# Actuator_Base_Board.net
KiCad netlist of a schematic drawn in Altium Designer
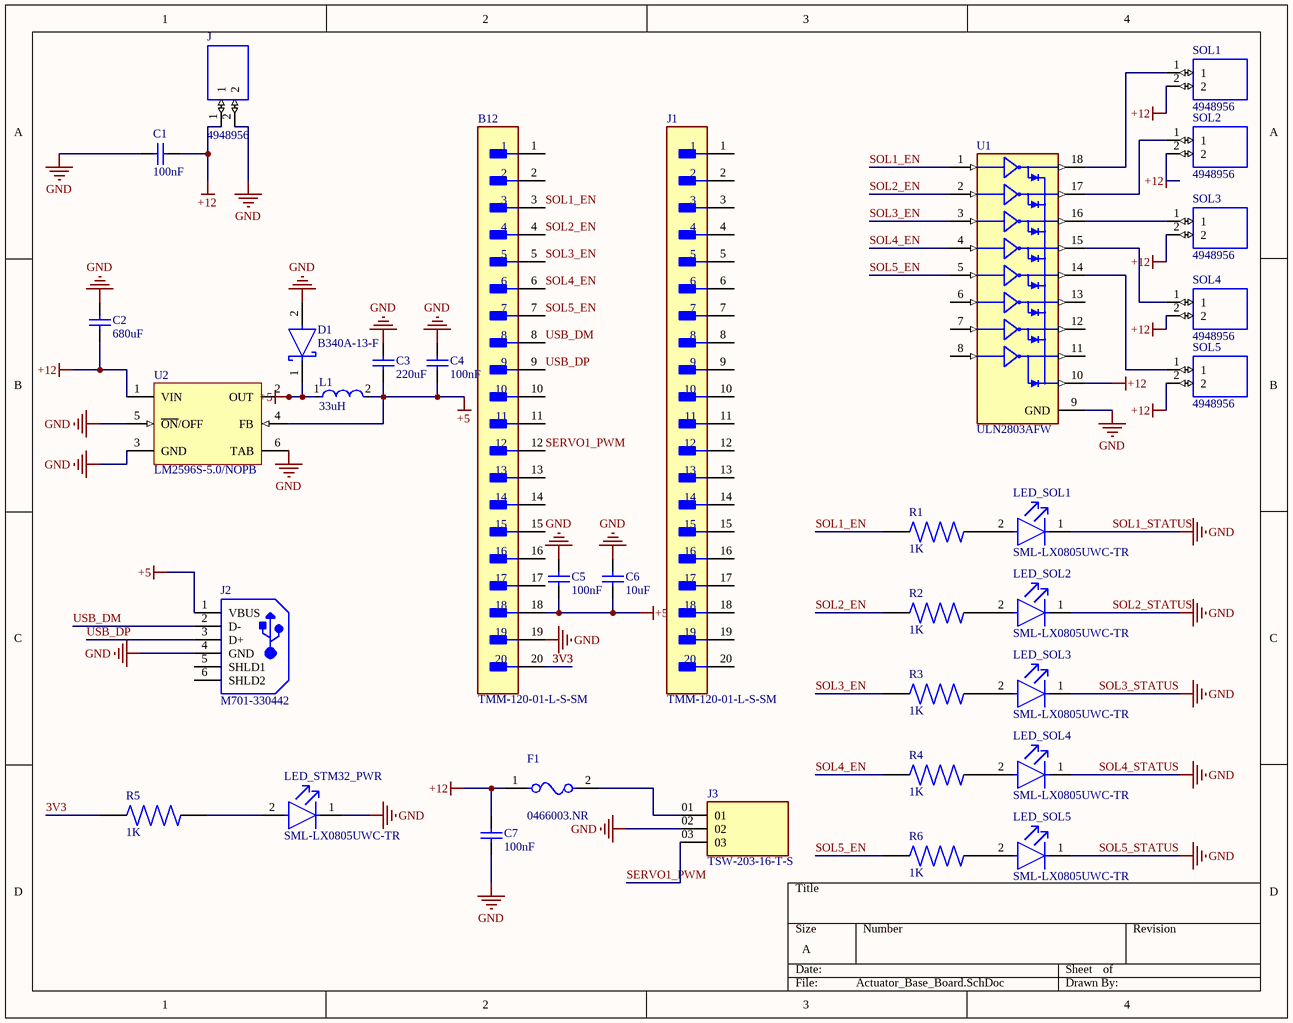
[diagram p0: Actuator_Base_Board.SchDoc]

(export (version "E")
  (design (tool "Eeschema 10.0.6"))
  (components
    (comp (ref "B12")
      (value "TMM-120-01-L-S-SM")
      (footprint "FP-TMM-120-01-L-S-SM-MFG")
      (description "2MM TERMINAL STRIP")
      (libsource (lib "Actuator_Base_Board") (part "CMP-02766-001494-1"))
    )
    (comp (ref "C1")
      (value "100nF")
      (footprint "CAPC2013X145X48LL20T23")
      (fields (field (name "MANUFACTURER") "Vitramon") (field (name "PART NUMBER") "VJ0805Y682KXAMT"))
      (libsource (lib "Actuator_Base_Board") (part "CMP-2007-03205-1"))
    )
    (comp (ref "C2")
      (value "680uF")
      (footprint "CAPC2013X145X48LL20T23")
      (fields (field (name "MANUFACTURER") "Vitramon") (field (name "PART NUMBER") "VJ0805Y682KXAMT"))
      (libsource (lib "Actuator_Base_Board") (part "CMP-2007-03205-1"))
    )
    (comp (ref "C3")
      (value "220uF")
      (footprint "CAPC2013X145X48LL20T23")
      (fields (field (name "MANUFACTURER") "Vitramon") (field (name "PART NUMBER") "VJ0805Y682KXAMT"))
      (libsource (lib "Actuator_Base_Board") (part "CMP-2007-03205-1"))
    )
    (comp (ref "C4")
      (value "100nF")
      (footprint "CAPC2013X145X48LL20T23")
      (fields (field (name "MANUFACTURER") "Vitramon") (field (name "PART NUMBER") "VJ0805Y682KXAMT"))
      (libsource (lib "Actuator_Base_Board") (part "CMP-2007-03205-1"))
    )
    (comp (ref "C5")
      (value "100nF")
      (footprint "CAPC2013X145X48LL20T23")
      (fields (field (name "MANUFACTURER") "Vitramon") (field (name "PART NUMBER") "VJ0805Y682KXAMT"))
      (libsource (lib "Actuator_Base_Board") (part "CMP-2007-03205-1"))
    )
    (comp (ref "C6")
      (value "10uF")
      (footprint "CAPC2013X145X48LL20T23")
      (fields (field (name "MANUFACTURER") "Vitramon") (field (name "PART NUMBER") "VJ0805Y682KXAMT"))
      (libsource (lib "Actuator_Base_Board") (part "CMP-2007-03205-1"))
    )
    (comp (ref "C7")
      (value "100nF")
      (footprint "CAPC2013X145X48LL20T23")
      (fields (field (name "MANUFACTURER") "Vitramon") (field (name "PART NUMBER") "VJ0805Y682KXAMT"))
      (libsource (lib "Actuator_Base_Board") (part "CMP-2007-03205-1"))
    )
    (comp (ref "D1")
      (value "B340A-13-F")
      (footprint "FP-SMA-MFG")
      (description "DIODE SCHOTTKY 40V 3A SMA")
      (fields (field (name "VOLTAGE") "40V"))
      (libsource (lib "Actuator_Base_Board") (part "CMP-1667-00003-3"))
    )
    (comp (ref "F1")
      (value "0466003.NR")
      (footprint "FP-0466-MFG")
      (description "FUSE BOARD MNT 3A 32VAC/VDC 1206")
      (fields
        (field (name "OCTOPART") "https://octopart.com/0466003.nr-littelfuse-565175")
        (field (name "MANUFACTURER") "Littelfuse")
      )
      (libsource (lib "Actuator_Base_Board") (part "CMP-08605-000054-1_1"))
    )
    (comp (ref "J")
      (value "4948956")
      (footprint "SHDR2W100P0X500_1X2_1000X750X1")
      (description "5.08mm Pitch Straight PCB Terminal Block with Screw Term.; Through Hole; 2 Way")
      (fields (field (name "MF") "RS Pro"))
      (libsource (lib "Actuator_Base_Board") (part "4948956"))
    )
    (comp (ref "J1")
      (value "TMM-120-01-L-S-SM")
      (footprint "FP-TMM-120-01-L-S-SM-MFG")
      (description "2MM TERMINAL STRIP")
      (libsource (lib "Actuator_Base_Board") (part "CMP-02766-001494-1"))
    )
    (comp (ref "J2")
      (value "M701-330442")
      (footprint "HRWN-M701-330442_V")
      (description "Single USB 2.0, Receptacle Connecter, B Type, 4 Position Through Hole, -55 to 85 degC, RoHS, Tray")
      (libsource (lib "Actuator_Base_Board") (part "CMP-1752-00001-1"))
    )
    (comp (ref "J3")
      (value "TSW-203-16-T-S")
      (footprint "SAMTEC_TSW-203-16-T-S")
      (libsource (lib "Actuator_Base_Board") (part "TSW-203-16-T-S"))
    )
    (comp (ref "L1")
      (value "33uH")
      (footprint "FP-NR4018-MFG")
      (description "SMD Power Inductors 220uH ±20% 0.17A 4.56Ω")
      (fields (field (name "TOLERANCE") "20%"))
      (libsource (lib "Actuator_Base_Board") (part "CMP-14484-001019-1"))
    )
    (comp (ref "LED_SOL1")
      (value "SML-LX0805UWC-TR")
      (footprint "FP-SML-LX0805UWC-TR-MFG")
      (description "SML-LX0805UWC-TR White LED, 0805 Diffused, Rectangle Lens SMD package ¦ Lumex SML-LX0805UWC-TR")
      (libsource (lib "Actuator_Base_Board") (part "CMP-00229-00139794-1"))
    )
    (comp (ref "LED_SOL2")
      (value "SML-LX0805UWC-TR")
      (footprint "FP-SML-LX0805UWC-TR-MFG")
      (description "SML-LX0805UWC-TR White LED, 0805 Diffused, Rectangle Lens SMD package ¦ Lumex SML-LX0805UWC-TR")
      (libsource (lib "Actuator_Base_Board") (part "CMP-00229-00139794-1"))
    )
    (comp (ref "LED_SOL3")
      (value "SML-LX0805UWC-TR")
      (footprint "FP-SML-LX0805UWC-TR-MFG")
      (description "SML-LX0805UWC-TR White LED, 0805 Diffused, Rectangle Lens SMD package ¦ Lumex SML-LX0805UWC-TR")
      (libsource (lib "Actuator_Base_Board") (part "CMP-00229-00139794-1"))
    )
    (comp (ref "LED_SOL4")
      (value "SML-LX0805UWC-TR")
      (footprint "FP-SML-LX0805UWC-TR-MFG")
      (description "SML-LX0805UWC-TR White LED, 0805 Diffused, Rectangle Lens SMD package ¦ Lumex SML-LX0805UWC-TR")
      (libsource (lib "Actuator_Base_Board") (part "CMP-00229-00139794-1"))
    )
    (comp (ref "LED_SOL5")
      (value "SML-LX0805UWC-TR")
      (footprint "FP-SML-LX0805UWC-TR-MFG")
      (description "SML-LX0805UWC-TR White LED, 0805 Diffused, Rectangle Lens SMD package ¦ Lumex SML-LX0805UWC-TR")
      (libsource (lib "Actuator_Base_Board") (part "CMP-00229-00139794-1"))
    )
    (comp (ref "LED_STM32_PWR")
      (value "SML-LX0805UWC-TR")
      (footprint "FP-SML-LX0805UWC-TR-MFG")
      (description "SML-LX0805UWC-TR White LED, 0805 Diffused, Rectangle Lens SMD package ¦ Lumex SML-LX0805UWC-TR")
      (libsource (lib "Actuator_Base_Board") (part "CMP-00229-00139794-1"))
    )
    (comp (ref "R1")
      (value "1K")
      (footprint "RES_ERJU02F1543X")
      (fields (field (name "MP") "ERJU02F1543X"))
      (libsource (lib "Actuator_Base_Board") (part "ERJU02F1543X"))
    )
    (comp (ref "R2")
      (value "1K")
      (footprint "RES_ERJU02F1543X")
      (fields (field (name "MP") "ERJU02F1543X"))
      (libsource (lib "Actuator_Base_Board") (part "ERJU02F1543X"))
    )
    (comp (ref "R3")
      (value "1K")
      (footprint "RES_ERJU02F1543X")
      (fields (field (name "MP") "ERJU02F1543X"))
      (libsource (lib "Actuator_Base_Board") (part "ERJU02F1543X"))
    )
    (comp (ref "R4")
      (value "1K")
      (footprint "RES_ERJU02F1543X")
      (fields (field (name "MP") "ERJU02F1543X"))
      (libsource (lib "Actuator_Base_Board") (part "ERJU02F1543X"))
    )
    (comp (ref "R5")
      (value "1K")
      (footprint "RES_ERJU02F1543X")
      (fields (field (name "MP") "ERJU02F1543X"))
      (libsource (lib "Actuator_Base_Board") (part "ERJU02F1543X"))
    )
    (comp (ref "R6")
      (value "1K")
      (footprint "RES_ERJU02F1543X")
      (fields (field (name "MP") "ERJU02F1543X"))
      (libsource (lib "Actuator_Base_Board") (part "ERJU02F1543X"))
    )
    (comp (ref "SOL1")
      (value "4948956")
      (footprint "SHDR2W100P0X500_1X2_1000X750X1")
      (description "5.08mm Pitch Straight PCB Terminal Block with Screw Term.; Through Hole; 2 Way")
      (fields (field (name "MF") "RS Pro"))
      (libsource (lib "Actuator_Base_Board") (part "4948956"))
    )
    (comp (ref "SOL2")
      (value "4948956")
      (footprint "SHDR2W100P0X500_1X2_1000X750X1")
      (description "5.08mm Pitch Straight PCB Terminal Block with Screw Term.; Through Hole; 2 Way")
      (fields (field (name "MF") "RS Pro"))
      (libsource (lib "Actuator_Base_Board") (part "4948956"))
    )
    (comp (ref "SOL3")
      (value "4948956")
      (footprint "SHDR2W100P0X500_1X2_1000X750X1")
      (description "5.08mm Pitch Straight PCB Terminal Block with Screw Term.; Through Hole; 2 Way")
      (fields (field (name "MF") "RS Pro"))
      (libsource (lib "Actuator_Base_Board") (part "4948956"))
    )
    (comp (ref "SOL4")
      (value "4948956")
      (footprint "SHDR2W100P0X500_1X2_1000X750X1")
      (description "5.08mm Pitch Straight PCB Terminal Block with Screw Term.; Through Hole; 2 Way")
      (fields (field (name "MF") "RS Pro"))
      (libsource (lib "Actuator_Base_Board") (part "4948956"))
    )
    (comp (ref "SOL5")
      (value "4948956")
      (footprint "SHDR2W100P0X500_1X2_1000X750X1")
      (description "5.08mm Pitch Straight PCB Terminal Block with Screw Term.; Through Hole; 2 Way")
      (fields (field (name "MF") "RS Pro"))
      (libsource (lib "Actuator_Base_Board") (part "4948956"))
    )
    (comp (ref "U1")
      (value "ULN2803AFW")
      (footprint "SOIC127P1030X265-18N")
      (description "Bipolar (BJT) Transistor Array 8 NPN Darlington 50V 500mA - 1.31W Surface Mount 18-SOP")
      (fields (field (name "MF") "Toshiba"))
      (libsource (lib "Actuator_Base_Board") (part "ULN2803AFW"))
    )
    (comp (ref "U2")
      (value "LM2596S-5.0/NOPB")
      (footprint "KTT0005B_L")
      (description "SIMPLE SWITCHER® Power Converter 150 KHz 3A Step-Down Voltage Regulator, 5-pin TO-263, Pb-Free")
      (fields (field (name "MANUFACTURER") "Texas Instruments"))
      (libsource (lib "Actuator_Base_Board") (part "CMP-0069-00269-3"))
    )
  )
  (nets
    (net (code "1") (name "+5") (class "Default")
      (node (ref "B12") (pin "18") (pinfunction "18_18") (pintype "passive"))
      (node (ref "C3") (pin "2") (pinfunction "2_2") (pintype "passive"))
      (node (ref "C4") (pin "1") (pinfunction "1_1") (pintype "passive"))
      (node (ref "C5") (pin "1") (pinfunction "1_1") (pintype "passive"))
      (node (ref "C6") (pin "1") (pinfunction "1_1") (pintype "passive"))
      (node (ref "D1") (pin "1") (pinfunction "C_1") (pintype "passive"))
      (node (ref "J2") (pin "1") (pinfunction "VBUS_1") (pintype "passive"))
      (node (ref "L1") (pin "1") (pinfunction "1_1") (pintype "passive"))
      (node (ref "L1") (pin "2") (pinfunction "2_2") (pintype "passive"))
      (node (ref "U2") (pin "2") (pinfunction "OUT_2") (pintype "power_in"))
      (node (ref "U2") (pin "4") (pinfunction "FB_4") (pintype "input"))
    )
    (net (code "2") (name "+12") (class "Default")
      (node (ref "C1") (pin "1") (pinfunction "1_1") (pintype "passive"))
      (node (ref "C2") (pin "1") (pinfunction "1_1") (pintype "passive"))
      (node (ref "C7") (pin "2") (pinfunction "2_2") (pintype "passive"))
      (node (ref "F1") (pin "1") (pinfunction "1_1") (pintype "passive"))
      (node (ref "J") (pin "1") (pinfunction "1_1") (pintype "bidirectional"))
      (node (ref "SOL1") (pin "2") (pinfunction "2_2") (pintype "bidirectional"))
      (node (ref "SOL2") (pin "2") (pinfunction "2_2") (pintype "bidirectional"))
      (node (ref "SOL3") (pin "2") (pinfunction "2_2") (pintype "bidirectional"))
      (node (ref "SOL4") (pin "2") (pinfunction "2_2") (pintype "bidirectional"))
      (node (ref "SOL5") (pin "2") (pinfunction "2_2") (pintype "bidirectional"))
      (node (ref "U1") (pin "10") (pinfunction "COMMON_10") (pintype "output"))
      (node (ref "U2") (pin "1") (pinfunction "VIN_1") (pintype "power_in"))
    )
    (net (code "3") (name "/3V3") (class "Default")
      (node (ref "B12") (pin "20") (pinfunction "20_20") (pintype "passive"))
      (node (ref "R5") (pin "1") (pinfunction "1_1") (pintype "passive"))
    )
    (net (code "5") (name "/SERVO1_PWM") (class "Default")
      (node (ref "B12") (pin "12") (pinfunction "12_12") (pintype "passive"))
      (node (ref "J3") (pin "03") (pinfunction "03_03") (pintype "passive"))
    )
    (net (code "6") (name "/SOL1_EN") (class "Default")
      (node (ref "B12") (pin "3") (pinfunction "3_3") (pintype "passive"))
      (node (ref "R1") (pin "1") (pinfunction "1_1") (pintype "passive"))
      (node (ref "U1") (pin "1") (pinfunction "I1_1") (pintype "input"))
    )
    (net (code "7") (name "/SOL2_EN") (class "Default")
      (node (ref "B12") (pin "4") (pinfunction "4_4") (pintype "passive"))
      (node (ref "R2") (pin "1") (pinfunction "1_1") (pintype "passive"))
      (node (ref "U1") (pin "2") (pinfunction "I2_2") (pintype "input"))
    )
    (net (code "8") (name "/SOL3_EN") (class "Default")
      (node (ref "B12") (pin "5") (pinfunction "5_5") (pintype "passive"))
      (node (ref "R3") (pin "1") (pinfunction "1_1") (pintype "passive"))
      (node (ref "U1") (pin "3") (pinfunction "I3_3") (pintype "input"))
    )
    (net (code "9") (name "/SOL4_EN") (class "Default")
      (node (ref "B12") (pin "6") (pinfunction "6_6") (pintype "passive"))
      (node (ref "R4") (pin "1") (pinfunction "1_1") (pintype "passive"))
      (node (ref "U1") (pin "4") (pinfunction "I4_4") (pintype "input"))
    )
    (net (code "10") (name "/SOL5_EN") (class "Default")
      (node (ref "B12") (pin "7") (pinfunction "7_7") (pintype "passive"))
      (node (ref "R6") (pin "1") (pinfunction "1_1") (pintype "passive"))
      (node (ref "U1") (pin "5") (pinfunction "I5_5") (pintype "input"))
    )
    (net (code "11") (name "/USB_DM") (class "Default")
      (node (ref "B12") (pin "8") (pinfunction "8_8") (pintype "passive"))
      (node (ref "J2") (pin "2") (pinfunction "D-_2") (pintype "passive"))
    )
    (net (code "12") (name "/USB_DP") (class "Default")
      (node (ref "B12") (pin "9") (pinfunction "9_9") (pintype "passive"))
      (node (ref "J2") (pin "3") (pinfunction "D+_3") (pintype "passive"))
    )
    (net (code "13") (name "GND") (class "Default")
      (node (ref "B12") (pin "19") (pinfunction "19_19") (pintype "passive"))
      (node (ref "C1") (pin "2") (pinfunction "2_2") (pintype "passive"))
      (node (ref "C2") (pin "2") (pinfunction "2_2") (pintype "passive"))
      (node (ref "C3") (pin "1") (pinfunction "1_1") (pintype "passive"))
      (node (ref "C4") (pin "2") (pinfunction "2_2") (pintype "passive"))
      (node (ref "C5") (pin "2") (pinfunction "2_2") (pintype "passive"))
      (node (ref "C6") (pin "2") (pinfunction "2_2") (pintype "passive"))
      (node (ref "C7") (pin "1") (pinfunction "1_1") (pintype "passive"))
      (node (ref "D1") (pin "2") (pinfunction "A_2") (pintype "passive"))
      (node (ref "J") (pin "2") (pinfunction "2_2") (pintype "bidirectional"))
      (node (ref "J2") (pin "4") (pinfunction "GND_4") (pintype "passive"))
      (node (ref "J3") (pin "02") (pinfunction "02_02") (pintype "passive"))
      (node (ref "LED_SOL1") (pin "1") (pinfunction "C_1") (pintype "passive"))
      (node (ref "LED_SOL2") (pin "1") (pinfunction "C_1") (pintype "passive"))
      (node (ref "LED_SOL3") (pin "1") (pinfunction "C_1") (pintype "passive"))
      (node (ref "LED_SOL4") (pin "1") (pinfunction "C_1") (pintype "passive"))
      (node (ref "LED_SOL5") (pin "1") (pinfunction "C_1") (pintype "passive"))
      (node (ref "LED_STM32_PWR") (pin "1") (pinfunction "C_1") (pintype "passive"))
      (node (ref "U1") (pin "9") (pinfunction "GND_9") (pintype "power_in"))
      (node (ref "U2") (pin "3") (pinfunction "GND_3") (pintype "power_in"))
      (node (ref "U2") (pin "5") (pinfunction "~{ON}/OFF_5") (pintype "input"))
      (node (ref "U2") (pin "6") (pinfunction "TAB_6") (pintype "power_in"))
    )
    (net (code "14") (name "Net-(F1-Pad2)") (class "Default")
      (node (ref "F1") (pin "2") (pinfunction "2_2") (pintype "passive"))
      (node (ref "J3") (pin "01") (pinfunction "01_01") (pintype "passive"))
    )
    (net (code "15") (name "Net-(LED_SOL1-A)") (class "Default")
      (node (ref "LED_SOL1") (pin "2") (pinfunction "A_2") (pintype "passive"))
      (node (ref "R1") (pin "2") (pinfunction "2_2") (pintype "passive"))
    )
    (net (code "16") (name "Net-(LED_SOL2-A)") (class "Default")
      (node (ref "LED_SOL2") (pin "2") (pinfunction "A_2") (pintype "passive"))
      (node (ref "R2") (pin "2") (pinfunction "2_2") (pintype "passive"))
    )
    (net (code "17") (name "Net-(LED_SOL3-A)") (class "Default")
      (node (ref "LED_SOL3") (pin "2") (pinfunction "A_2") (pintype "passive"))
      (node (ref "R3") (pin "2") (pinfunction "2_2") (pintype "passive"))
    )
    (net (code "18") (name "Net-(LED_SOL4-A)") (class "Default")
      (node (ref "LED_SOL4") (pin "2") (pinfunction "A_2") (pintype "passive"))
      (node (ref "R4") (pin "2") (pinfunction "2_2") (pintype "passive"))
    )
    (net (code "19") (name "Net-(LED_SOL5-A)") (class "Default")
      (node (ref "LED_SOL5") (pin "2") (pinfunction "A_2") (pintype "passive"))
      (node (ref "R6") (pin "2") (pinfunction "2_2") (pintype "passive"))
    )
    (net (code "20") (name "Net-(LED_STM32_PWR-A)") (class "Default")
      (node (ref "LED_STM32_PWR") (pin "2") (pinfunction "A_2") (pintype "passive"))
      (node (ref "R5") (pin "2") (pinfunction "2_2") (pintype "passive"))
    )
    (net (code "21") (name "Net-(U1-O1)") (class "Default")
      (node (ref "SOL1") (pin "1") (pinfunction "1_1") (pintype "bidirectional"))
      (node (ref "U1") (pin "18") (pinfunction "O1_18") (pintype "output"))
    )
    (net (code "22") (name "Net-(U1-O2)") (class "Default")
      (node (ref "SOL2") (pin "1") (pinfunction "1_1") (pintype "bidirectional"))
      (node (ref "U1") (pin "17") (pinfunction "O2_17") (pintype "output"))
    )
    (net (code "23") (name "Net-(U1-O3)") (class "Default")
      (node (ref "SOL3") (pin "1") (pinfunction "1_1") (pintype "bidirectional"))
      (node (ref "U1") (pin "16") (pinfunction "O3_16") (pintype "output"))
    )
    (net (code "24") (name "Net-(U1-O4)") (class "Default")
      (node (ref "SOL4") (pin "1") (pinfunction "1_1") (pintype "bidirectional"))
      (node (ref "U1") (pin "15") (pinfunction "O4_15") (pintype "output"))
    )
    (net (code "25") (name "Net-(U1-O5)") (class "Default")
      (node (ref "SOL5") (pin "1") (pinfunction "1_1") (pintype "bidirectional"))
      (node (ref "U1") (pin "14") (pinfunction "O5_14") (pintype "output"))
    )
    (net (code "26") (name "unconnected-(B12-Pad1)") (class "Default")
      (node (ref "B12") (pin "1") (pinfunction "1_1") (pintype "passive"))
    )
    (net (code "27") (name "unconnected-(B12-Pad2)") (class "Default")
      (node (ref "B12") (pin "2") (pinfunction "2_2") (pintype "passive"))
    )
    (net (code "28") (name "unconnected-(B12-Pad10)") (class "Default")
      (node (ref "B12") (pin "10") (pinfunction "10_10") (pintype "passive"))
    )
    (net (code "29") (name "unconnected-(B12-Pad11)") (class "Default")
      (node (ref "B12") (pin "11") (pinfunction "11_11") (pintype "passive"))
    )
    (net (code "30") (name "unconnected-(B12-Pad13)") (class "Default")
      (node (ref "B12") (pin "13") (pinfunction "13_13") (pintype "passive"))
    )
    (net (code "31") (name "unconnected-(B12-Pad14)") (class "Default")
      (node (ref "B12") (pin "14") (pinfunction "14_14") (pintype "passive"))
    )
    (net (code "32") (name "unconnected-(B12-Pad15)") (class "Default")
      (node (ref "B12") (pin "15") (pinfunction "15_15") (pintype "passive"))
    )
    (net (code "33") (name "unconnected-(B12-Pad16)") (class "Default")
      (node (ref "B12") (pin "16") (pinfunction "16_16") (pintype "passive"))
    )
    (net (code "34") (name "unconnected-(B12-Pad17)") (class "Default")
      (node (ref "B12") (pin "17") (pinfunction "17_17") (pintype "passive"))
    )
    (net (code "35") (name "unconnected-(J1-Pad1)") (class "Default")
      (node (ref "J1") (pin "1") (pinfunction "1_1") (pintype "passive"))
    )
    (net (code "36") (name "unconnected-(J1-Pad2)") (class "Default")
      (node (ref "J1") (pin "2") (pinfunction "2_2") (pintype "passive"))
    )
    (net (code "37") (name "unconnected-(J1-Pad3)") (class "Default")
      (node (ref "J1") (pin "3") (pinfunction "3_3") (pintype "passive"))
    )
    (net (code "38") (name "unconnected-(J1-Pad4)") (class "Default")
      (node (ref "J1") (pin "4") (pinfunction "4_4") (pintype "passive"))
    )
    (net (code "39") (name "unconnected-(J1-Pad5)") (class "Default")
      (node (ref "J1") (pin "5") (pinfunction "5_5") (pintype "passive"))
    )
    (net (code "40") (name "unconnected-(J1-Pad6)") (class "Default")
      (node (ref "J1") (pin "6") (pinfunction "6_6") (pintype "passive"))
    )
    (net (code "41") (name "unconnected-(J1-Pad7)") (class "Default")
      (node (ref "J1") (pin "7") (pinfunction "7_7") (pintype "passive"))
    )
    (net (code "42") (name "unconnected-(J1-Pad8)") (class "Default")
      (node (ref "J1") (pin "8") (pinfunction "8_8") (pintype "passive"))
    )
    (net (code "43") (name "unconnected-(J1-Pad9)") (class "Default")
      (node (ref "J1") (pin "9") (pinfunction "9_9") (pintype "passive"))
    )
    (net (code "44") (name "unconnected-(J1-Pad10)") (class "Default")
      (node (ref "J1") (pin "10") (pinfunction "10_10") (pintype "passive"))
    )
    (net (code "45") (name "unconnected-(J1-Pad11)") (class "Default")
      (node (ref "J1") (pin "11") (pinfunction "11_11") (pintype "passive"))
    )
    (net (code "46") (name "unconnected-(J1-Pad12)") (class "Default")
      (node (ref "J1") (pin "12") (pinfunction "12_12") (pintype "passive"))
    )
    (net (code "47") (name "unconnected-(J1-Pad13)") (class "Default")
      (node (ref "J1") (pin "13") (pinfunction "13_13") (pintype "passive"))
    )
    (net (code "48") (name "unconnected-(J1-Pad14)") (class "Default")
      (node (ref "J1") (pin "14") (pinfunction "14_14") (pintype "passive"))
    )
    (net (code "49") (name "unconnected-(J1-Pad15)") (class "Default")
      (node (ref "J1") (pin "15") (pinfunction "15_15") (pintype "passive"))
    )
    (net (code "50") (name "unconnected-(J1-Pad16)") (class "Default")
      (node (ref "J1") (pin "16") (pinfunction "16_16") (pintype "passive"))
    )
    (net (code "51") (name "unconnected-(J1-Pad17)") (class "Default")
      (node (ref "J1") (pin "17") (pinfunction "17_17") (pintype "passive"))
    )
    (net (code "52") (name "unconnected-(J1-Pad18)") (class "Default")
      (node (ref "J1") (pin "18") (pinfunction "18_18") (pintype "passive"))
    )
    (net (code "53") (name "unconnected-(J1-Pad19)") (class "Default")
      (node (ref "J1") (pin "19") (pinfunction "19_19") (pintype "passive"))
    )
    (net (code "54") (name "unconnected-(J1-Pad20)") (class "Default")
      (node (ref "J1") (pin "20") (pinfunction "20_20") (pintype "passive"))
    )
    (net (code "55") (name "unconnected-(J2-SHLD1-Pad5)") (class "Default")
      (node (ref "J2") (pin "5") (pinfunction "SHLD1_5") (pintype "passive"))
    )
    (net (code "56") (name "unconnected-(J2-SHLD2-Pad6)") (class "Default")
      (node (ref "J2") (pin "6") (pinfunction "SHLD2_6") (pintype "passive"))
    )
    (net (code "57") (name "unconnected-(U1-I6-Pad6)") (class "Default")
      (node (ref "U1") (pin "6") (pinfunction "I6_6") (pintype "input"))
    )
    (net (code "58") (name "unconnected-(U1-I7-Pad7)") (class "Default")
      (node (ref "U1") (pin "7") (pinfunction "I7_7") (pintype "input"))
    )
    (net (code "59") (name "unconnected-(U1-I8-Pad8)") (class "Default")
      (node (ref "U1") (pin "8") (pinfunction "I8_8") (pintype "input"))
    )
    (net (code "60") (name "unconnected-(U1-O6-Pad13)") (class "Default")
      (node (ref "U1") (pin "13") (pinfunction "O6_13") (pintype "output"))
    )
    (net (code "61") (name "unconnected-(U1-O7-Pad12)") (class "Default")
      (node (ref "U1") (pin "12") (pinfunction "O7_12") (pintype "output"))
    )
    (net (code "62") (name "unconnected-(U1-O8-Pad11)") (class "Default")
      (node (ref "U1") (pin "11") (pinfunction "O8_11") (pintype "output"))
    )
  )
)
